# Infinity_Mirror_c_unbuilt.net
KiCad netlist of a schematic drawn in EAGLE
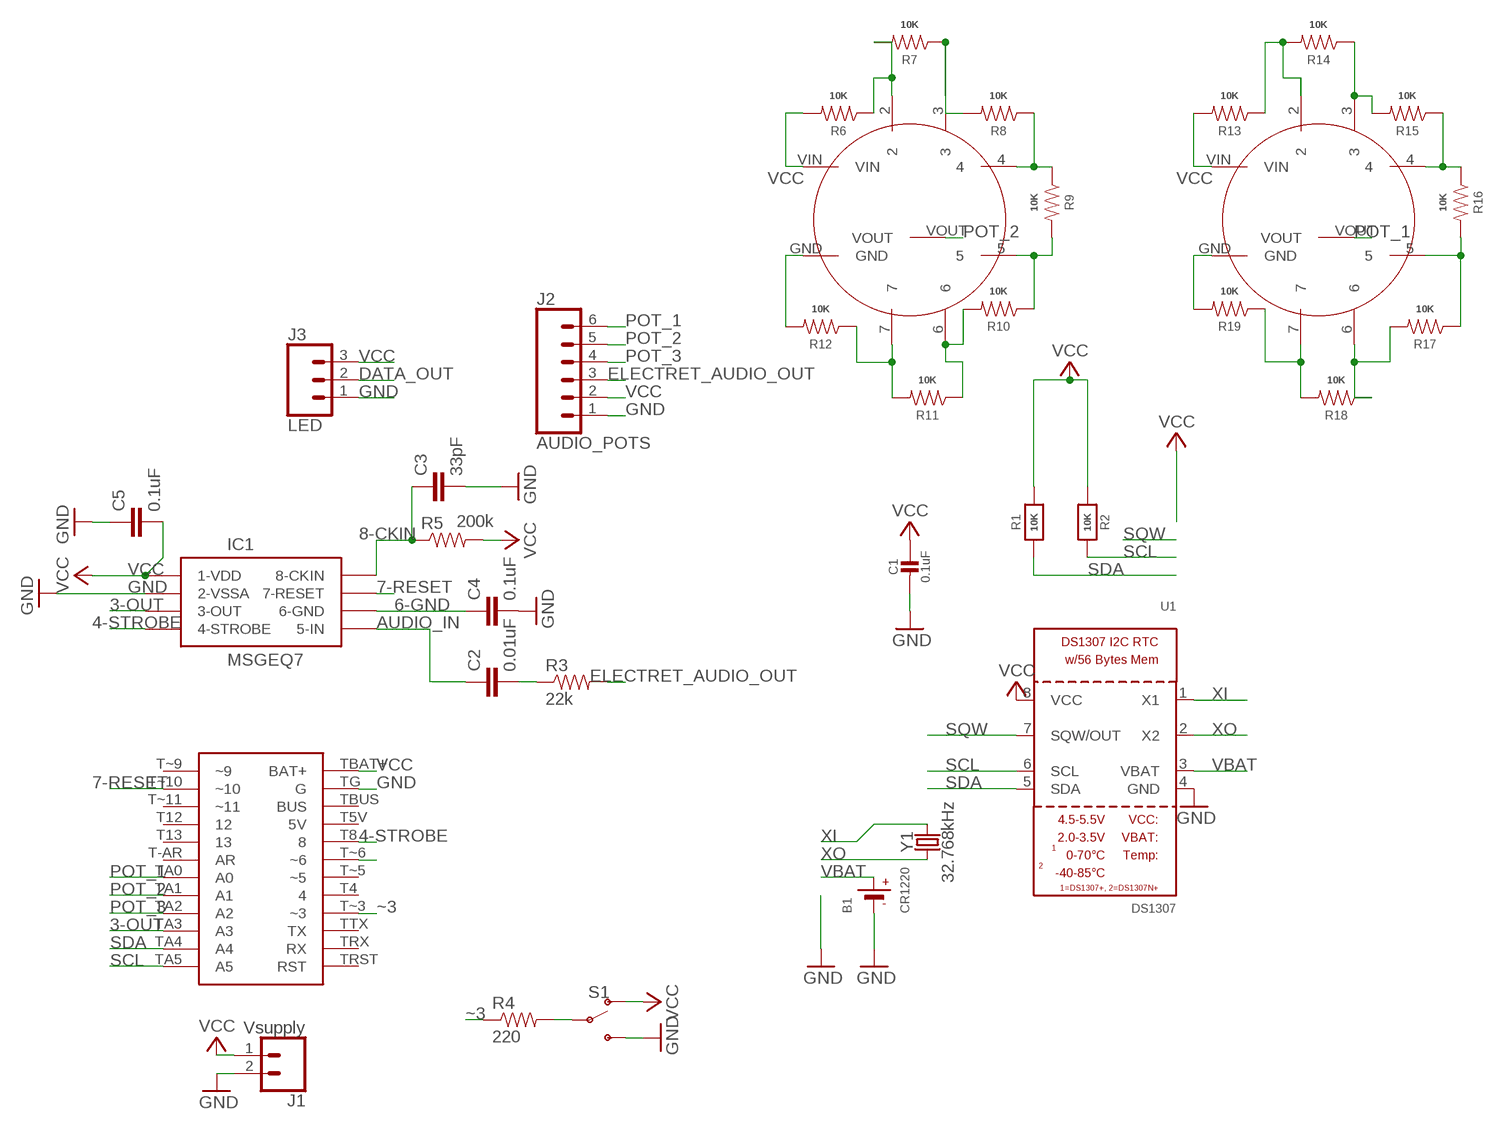
[diagram p0: schematic, sheet 1]

(export (version "E")
  (design (tool "Eeschema 10.0.6"))
  (components
    (comp (ref "B1")
      (value "CR1220")
      (footprint "eagle-import:CR1220")
      (libsource (lib "eagle-import") (part "BATTERYCR1220_SMT"))
    )
    (comp (ref "C1")
      (value "0.1uF")
      (footprint "eagle-import:0805-NO")
      (libsource (lib "eagle-import") (part "CAP_CERAMIC0805-NOOUTLINE"))
    )
    (comp (ref "C2")
      (value "0.01uF")
      (footprint "eagle-import:SPARKFUN-CAPACITORS_0805")
      (libsource (lib "eagle-import") (part "SPARKFUN-CAPACITORS_CAP0805"))
    )
    (comp (ref "C3")
      (value "33pF")
      (footprint "eagle-import:0805")
      (libsource (lib "eagle-import") (part "0.33UF/330NF-0805-50V-10%"))
    )
    (comp (ref "C4")
      (value "0.1uF")
      (footprint "eagle-import:SPARKFUN-CAPACITORS_0805")
      (libsource (lib "eagle-import") (part "SPARKFUN-CAPACITORS_CAP0805"))
    )
    (comp (ref "C5")
      (value "0.1uF")
      (footprint "eagle-import:SPARKFUN-CAPACITORS_0805")
      (libsource (lib "eagle-import") (part "SPARKFUN-CAPACITORS_CAP0805"))
    )
    (comp (ref "IC1")
      (value "MSGEQ7P")
      (footprint "eagle-import:DIP08")
      (libsource (lib "eagle-import") (part "MSGEQ7DIL"))
    )
    (comp (ref "J1")
      (value "Vsupply")
      (footprint "eagle-import:SPARKFUN-CONNECTORS_1X02_LOCK")
      (libsource (lib "eagle-import") (part "SPARKFUN-CONNECTORS_CONN_02LOCK"))
    )
    (comp (ref "J2")
      (value "AUDIO_POTS")
      (footprint "eagle-import:1X06")
      (libsource (lib "eagle-import") (part "CONN_06SILK_FEMALE_PTH"))
    )
    (comp (ref "J3")
      (value "LED")
      (footprint "eagle-import:1X03")
      (libsource (lib "eagle-import") (part "CONN_03"))
    )
    (comp (ref "R1")
      (value "10K")
      (footprint "eagle-import:0805-NO")
      (libsource (lib "eagle-import") (part "RESISTOR0805_NOOUTLINE"))
    )
    (comp (ref "R2")
      (value "10K")
      (footprint "eagle-import:0805-NO")
      (libsource (lib "eagle-import") (part "RESISTOR0805_NOOUTLINE"))
    )
    (comp (ref "R3")
      (value "22k")
      (footprint "eagle-import:SPARKFUN-PASSIVES_0805")
      (libsource (lib "eagle-import") (part "SPARKFUN-PASSIVES_RESISTOR0805-RES"))
    )
    (comp (ref "R4")
      (value "220")
      (footprint "eagle-import:SPARKFUN-PASSIVES_0805")
      (libsource (lib "eagle-import") (part "SPARKFUN-PASSIVES_RESISTOR0805-RES"))
    )
    (comp (ref "R5")
      (value "200k")
      (footprint "eagle-import:SPARKFUN-PASSIVES_0805")
      (libsource (lib "eagle-import") (part "SPARKFUN-PASSIVES_RESISTOR0805-RES"))
    )
    (comp (ref "R6")
      (value "10K")
      (footprint "eagle-import:SPARKFUN-PASSIVES_0805")
      (libsource (lib "eagle-import") (part "SPARKFUN-PASSIVES_RESISTOR0805-RES"))
    )
    (comp (ref "R7")
      (value "10K")
      (footprint "eagle-import:SPARKFUN-PASSIVES_0805")
      (libsource (lib "eagle-import") (part "SPARKFUN-PASSIVES_RESISTOR0805-RES"))
    )
    (comp (ref "R8")
      (value "10K")
      (footprint "eagle-import:SPARKFUN-PASSIVES_0805")
      (libsource (lib "eagle-import") (part "SPARKFUN-PASSIVES_RESISTOR0805-RES"))
    )
    (comp (ref "R9")
      (value "10K")
      (footprint "eagle-import:SPARKFUN-PASSIVES_0805")
      (libsource (lib "eagle-import") (part "SPARKFUN-PASSIVES_RESISTOR0805-RES"))
    )
    (comp (ref "R10")
      (value "10K")
      (footprint "eagle-import:SPARKFUN-PASSIVES_0805")
      (libsource (lib "eagle-import") (part "SPARKFUN-PASSIVES_RESISTOR0805-RES"))
    )
    (comp (ref "R11")
      (value "10K")
      (footprint "eagle-import:SPARKFUN-PASSIVES_0805")
      (libsource (lib "eagle-import") (part "SPARKFUN-PASSIVES_RESISTOR0805-RES"))
    )
    (comp (ref "R12")
      (value "10K")
      (footprint "eagle-import:SPARKFUN-PASSIVES_0805")
      (libsource (lib "eagle-import") (part "SPARKFUN-PASSIVES_RESISTOR0805-RES"))
    )
    (comp (ref "R13")
      (value "10K")
      (footprint "eagle-import:SPARKFUN-PASSIVES_0805")
      (libsource (lib "eagle-import") (part "SPARKFUN-PASSIVES_RESISTOR0805-RES"))
    )
    (comp (ref "R14")
      (value "10K")
      (footprint "eagle-import:SPARKFUN-PASSIVES_0805")
      (libsource (lib "eagle-import") (part "SPARKFUN-PASSIVES_RESISTOR0805-RES"))
    )
    (comp (ref "R15")
      (value "10K")
      (footprint "eagle-import:SPARKFUN-PASSIVES_0805")
      (libsource (lib "eagle-import") (part "SPARKFUN-PASSIVES_RESISTOR0805-RES"))
    )
    (comp (ref "R16")
      (value "10K")
      (footprint "eagle-import:SPARKFUN-PASSIVES_0805")
      (libsource (lib "eagle-import") (part "SPARKFUN-PASSIVES_RESISTOR0805-RES"))
    )
    (comp (ref "R17")
      (value "10K")
      (footprint "eagle-import:SPARKFUN-PASSIVES_0805")
      (libsource (lib "eagle-import") (part "SPARKFUN-PASSIVES_RESISTOR0805-RES"))
    )
    (comp (ref "R18")
      (value "10K")
      (footprint "eagle-import:SPARKFUN-PASSIVES_0805")
      (libsource (lib "eagle-import") (part "SPARKFUN-PASSIVES_RESISTOR0805-RES"))
    )
    (comp (ref "R19")
      (value "10K")
      (footprint "eagle-import:SPARKFUN-PASSIVES_0805")
      (libsource (lib "eagle-import") (part "SPARKFUN-PASSIVES_RESISTOR0805-RES"))
    )
    (comp (ref "S1")
      (value "SWITCH-SPDT-PTH-11.6X4.0MM-LOCK")
      (footprint "eagle-import:SWITCH_SPDT_PTH_11.6X4.0MM_LOCK")
      (libsource (lib "eagle-import") (part "SWITCH-SPDT-PTH-11.6X4.0MM-LOCK"))
    )
    (comp (ref "U$1")
      (value "ADAFRUIT_PRO_TRINKET_NO-DIMENSION")
      (footprint "eagle-import:ARDUINO_PRO_TRINKET_5V_NO-DIMENSION")
      (libsource (lib "eagle-import") (part "ADAFRUIT_PRO_TRINKET_NO-DIMENSION"))
    )
    (comp (ref "U$2")
      (value "ROTARY-SWITCH-8POS")
      (footprint "eagle-import:ROTARY-SWITCH-8POS")
      (libsource (lib "eagle-import") (part "ROTARY-SWITCH-8POS"))
    )
    (comp (ref "U$3")
      (value "ROTARY-SWITCH-8POS")
      (footprint "eagle-import:ROTARY-SWITCH-8POS")
      (libsource (lib "eagle-import") (part "ROTARY-SWITCH-8POS"))
    )
    (comp (ref "U1")
      (value "DS1307")
      (footprint "eagle-import:SOIC8_150MIL")
      (libsource (lib "eagle-import") (part "RTC_DS1307"))
    )
    (comp (ref "Y1")
      (value "32.768kHz")
      (footprint "eagle-import:CRYSTAL-PTH-2X6-CYL")
      (libsource (lib "eagle-import") (part "CRYSTAL-32.768KHZPTH-2X6"))
    )
  )
  (nets
    (net (code "1") (name "/3-OUT") (class "Default")
      (node (ref "IC1") (pin "3") (pinfunction "3-OUT_3") (pintype "input"))
      (node (ref "U$1") (pin "TA3") (pinfunction "A3_TA3") (pintype "bidirectional"))
    )
    (net (code "2") (name "/4-STROBE") (class "Default")
      (node (ref "IC1") (pin "4") (pinfunction "4-STROBE_4") (pintype "input"))
      (node (ref "U$1") (pin "T8") (pinfunction "8_T8") (pintype "bidirectional"))
    )
    (net (code "3") (name "/6-GND") (class "Default")
      (node (ref "C4") (pin "1") (pinfunction "1_1") (pintype "passive"))
      (node (ref "IC1") (pin "6") (pinfunction "6-GND_6") (pintype "bidirectional"))
    )
    (net (code "4") (name "/7-RESET") (class "Default")
      (node (ref "IC1") (pin "7") (pinfunction "7-RESET_7") (pintype "bidirectional"))
      (node (ref "U$1") (pin "T~10") (pinfunction "~{10}_T~10") (pintype "bidirectional"))
    )
    (net (code "5") (name "/8-CKIN") (class "Default")
      (node (ref "C3") (pin "1") (pinfunction "1_1") (pintype "passive"))
      (node (ref "IC1") (pin "8") (pinfunction "8-CKIN_8") (pintype "bidirectional"))
      (node (ref "R5") (pin "1") (pinfunction "1_1") (pintype "passive"))
    )
    (net (code "6") (name "/AUDIO_IN") (class "Default")
      (node (ref "C2") (pin "1") (pinfunction "1_1") (pintype "passive"))
      (node (ref "IC1") (pin "5") (pinfunction "5-IN_5") (pintype "bidirectional"))
    )
    (net (code "7") (name "/DATA_OUT") (class "Default")
      (node (ref "J3") (pin "2") (pinfunction "2_2") (pintype "passive"))
      (node (ref "U$1") (pin "T~6") (pinfunction "~{6}_T~6") (pintype "bidirectional"))
    )
    (net (code "8") (name "/ELECTRET_AUDIO_OUT") (class "Default")
      (node (ref "J2") (pin "3") (pinfunction "3_3") (pintype "passive"))
      (node (ref "R3") (pin "2") (pinfunction "2_2") (pintype "passive"))
    )
    (net (code "9") (name "/POT_1") (class "Default")
      (node (ref "J2") (pin "6") (pinfunction "6_6") (pintype "passive"))
      (node (ref "U$1") (pin "TA0") (pinfunction "A0_TA0") (pintype "bidirectional"))
      (node (ref "U$3") (pin "VOUT") (pinfunction "VOUT_VOUT") (pintype "bidirectional"))
    )
    (net (code "10") (name "/POT_2") (class "Default")
      (node (ref "J2") (pin "5") (pinfunction "5_5") (pintype "passive"))
      (node (ref "U$1") (pin "TA1") (pinfunction "A1_TA1") (pintype "bidirectional"))
      (node (ref "U$2") (pin "VOUT") (pinfunction "VOUT_VOUT") (pintype "bidirectional"))
    )
    (net (code "11") (name "/POT_3") (class "Default")
      (node (ref "J2") (pin "4") (pinfunction "4_4") (pintype "passive"))
      (node (ref "U$1") (pin "TA2") (pinfunction "A2_TA2") (pintype "bidirectional"))
    )
    (net (code "12") (name "/SCL") (class "Default")
      (node (ref "R2") (pin "2") (pinfunction "2_2") (pintype "passive"))
      (node (ref "U$1") (pin "TA5") (pinfunction "A5_TA5") (pintype "bidirectional"))
      (node (ref "U1") (pin "6") (pinfunction "SCL_6") (pintype "bidirectional"))
    )
    (net (code "13") (name "/SDA") (class "Default")
      (node (ref "R1") (pin "1") (pinfunction "1_1") (pintype "passive"))
      (node (ref "U$1") (pin "TA4") (pinfunction "A4_TA4") (pintype "bidirectional"))
      (node (ref "U1") (pin "5") (pinfunction "SDA_5") (pintype "bidirectional"))
    )
    (net (code "14") (name "/SQW") (class "Default")
      (node (ref "U1") (pin "7") (pinfunction "SQW/OUT_7") (pintype "bidirectional"))
    )
    (net (code "15") (name "/VBAT") (class "Default")
      (node (ref "B1") (pin "+$1") (pinfunction "+_+$1") (pintype "passive"))
      (node (ref "U1") (pin "3") (pinfunction "VBAT_3") (pintype "bidirectional"))
    )
    (net (code "16") (name "/XI") (class "Default")
      (node (ref "U1") (pin "1") (pinfunction "X1_1") (pintype "bidirectional"))
      (node (ref "Y1") (pin "2") (pinfunction "2_2") (pintype "passive"))
    )
    (net (code "17") (name "/XO") (class "Default")
      (node (ref "U1") (pin "2") (pinfunction "X2_2") (pintype "bidirectional"))
      (node (ref "Y1") (pin "1") (pinfunction "1_1") (pintype "passive"))
    )
    (net (code "18") (name "/~{3}") (class "Default")
      (node (ref "R4") (pin "1") (pinfunction "1_1") (pintype "passive"))
      (node (ref "U$1") (pin "T~3") (pinfunction "~{3}_T~3") (pintype "bidirectional"))
    )
    (net (code "19") (name "GND") (class "Default")
      (node (ref "B1") (pin "-") (pinfunction "-_-") (pintype "passive"))
      (node (ref "C1") (pin "2") (pinfunction "2_2") (pintype "passive"))
      (node (ref "C3") (pin "2") (pinfunction "2_2") (pintype "passive"))
      (node (ref "C4") (pin "2") (pinfunction "2_2") (pintype "passive"))
      (node (ref "C5") (pin "1") (pinfunction "1_1") (pintype "passive"))
      (node (ref "IC1") (pin "2") (pinfunction "2-VSSA_2") (pintype "input"))
      (node (ref "J1") (pin "2") (pinfunction "2_2") (pintype "passive"))
      (node (ref "J2") (pin "1") (pinfunction "1_1") (pintype "passive"))
      (node (ref "J3") (pin "1") (pinfunction "1_1") (pintype "passive"))
      (node (ref "S1") (pin "3") (pinfunction "S_3") (pintype "passive"))
      (node (ref "U$1") (pin "TG") (pinfunction "G_TG") (pintype "bidirectional"))
      (node (ref "U1") (pin "4") (pinfunction "GND_4") (pintype "bidirectional"))
    )
    (net (code "20") (name "Net-(C2-Pad2)") (class "Default")
      (node (ref "C2") (pin "2") (pinfunction "2_2") (pintype "passive"))
      (node (ref "R3") (pin "1") (pinfunction "1_1") (pintype "passive"))
    )
    (net (code "21") (name "Net-(R6-Pad1)") (class "Default")
      (node (ref "R6") (pin "1") (pinfunction "1_1") (pintype "passive"))
      (node (ref "R7") (pin "2") (pinfunction "2_2") (pintype "passive"))
      (node (ref "U$2") (pin "2") (pinfunction "2_2") (pintype "bidirectional"))
    )
    (net (code "22") (name "Net-(R7-Pad1)") (class "Default")
      (node (ref "R7") (pin "1") (pinfunction "1_1") (pintype "passive"))
      (node (ref "R8") (pin "2") (pinfunction "2_2") (pintype "passive"))
      (node (ref "U$2") (pin "3") (pinfunction "3_3") (pintype "bidirectional"))
    )
    (net (code "23") (name "Net-(R8-Pad1)") (class "Default")
      (node (ref "R8") (pin "1") (pinfunction "1_1") (pintype "passive"))
      (node (ref "R9") (pin "1") (pinfunction "1_1") (pintype "passive"))
      (node (ref "U$2") (pin "4") (pinfunction "4_4") (pintype "bidirectional"))
    )
    (net (code "24") (name "Net-(R10-Pad1)") (class "Default")
      (node (ref "R10") (pin "1") (pinfunction "1_1") (pintype "passive"))
      (node (ref "R9") (pin "2") (pinfunction "2_2") (pintype "passive"))
      (node (ref "U$2") (pin "5") (pinfunction "5_5") (pintype "bidirectional"))
    )
    (net (code "25") (name "Net-(R10-Pad2)") (class "Default")
      (node (ref "R10") (pin "2") (pinfunction "2_2") (pintype "passive"))
      (node (ref "R11") (pin "1") (pinfunction "1_1") (pintype "passive"))
      (node (ref "U$2") (pin "6") (pinfunction "6_6") (pintype "bidirectional"))
    )
    (net (code "26") (name "Net-(R11-Pad2)") (class "Default")
      (node (ref "R11") (pin "2") (pinfunction "2_2") (pintype "passive"))
      (node (ref "R12") (pin "1") (pinfunction "1_1") (pintype "passive"))
      (node (ref "U$2") (pin "7") (pinfunction "7_7") (pintype "bidirectional"))
    )
    (net (code "27") (name "Net-(R12-Pad2)") (class "Default")
      (node (ref "R12") (pin "2") (pinfunction "2_2") (pintype "passive"))
      (node (ref "U$2") (pin "GND") (pinfunction "GND_GND") (pintype "bidirectional"))
    )
    (net (code "28") (name "Net-(R13-Pad1)") (class "Default")
      (node (ref "R13") (pin "1") (pinfunction "1_1") (pintype "passive"))
      (node (ref "R14") (pin "2") (pinfunction "2_2") (pintype "passive"))
      (node (ref "U$3") (pin "2") (pinfunction "2_2") (pintype "bidirectional"))
    )
    (net (code "29") (name "Net-(R14-Pad1)") (class "Default")
      (node (ref "R14") (pin "1") (pinfunction "1_1") (pintype "passive"))
      (node (ref "R15") (pin "2") (pinfunction "2_2") (pintype "passive"))
      (node (ref "U$3") (pin "3") (pinfunction "3_3") (pintype "bidirectional"))
    )
    (net (code "30") (name "Net-(R15-Pad1)") (class "Default")
      (node (ref "R15") (pin "1") (pinfunction "1_1") (pintype "passive"))
      (node (ref "R16") (pin "1") (pinfunction "1_1") (pintype "passive"))
      (node (ref "U$3") (pin "4") (pinfunction "4_4") (pintype "bidirectional"))
    )
    (net (code "31") (name "Net-(R16-Pad2)") (class "Default")
      (node (ref "R16") (pin "2") (pinfunction "2_2") (pintype "passive"))
      (node (ref "R17") (pin "1") (pinfunction "1_1") (pintype "passive"))
      (node (ref "U$3") (pin "5") (pinfunction "5_5") (pintype "bidirectional"))
    )
    (net (code "32") (name "Net-(R17-Pad2)") (class "Default")
      (node (ref "R17") (pin "2") (pinfunction "2_2") (pintype "passive"))
      (node (ref "R18") (pin "1") (pinfunction "1_1") (pintype "passive"))
      (node (ref "U$3") (pin "6") (pinfunction "6_6") (pintype "bidirectional"))
    )
    (net (code "33") (name "Net-(R18-Pad2)") (class "Default")
      (node (ref "R18") (pin "2") (pinfunction "2_2") (pintype "passive"))
      (node (ref "R19") (pin "1") (pinfunction "1_1") (pintype "passive"))
      (node (ref "U$3") (pin "7") (pinfunction "7_7") (pintype "bidirectional"))
    )
    (net (code "34") (name "Net-(R19-Pad2)") (class "Default")
      (node (ref "R19") (pin "2") (pinfunction "2_2") (pintype "passive"))
      (node (ref "U$3") (pin "GND") (pinfunction "GND_GND") (pintype "bidirectional"))
    )
    (net (code "35") (name "Net-(S1-P)") (class "Default")
      (node (ref "R4") (pin "2") (pinfunction "2_2") (pintype "passive"))
      (node (ref "S1") (pin "2") (pinfunction "P_2") (pintype "passive"))
    )
    (net (code "36") (name "VCC") (class "Default")
      (node (ref "C1") (pin "1") (pinfunction "1_1") (pintype "passive"))
      (node (ref "C5") (pin "2") (pinfunction "2_2") (pintype "passive"))
      (node (ref "IC1") (pin "1") (pinfunction "1-VDD_1") (pintype "input"))
      (node (ref "J1") (pin "1") (pinfunction "1_1") (pintype "passive"))
      (node (ref "J2") (pin "2") (pinfunction "2_2") (pintype "passive"))
      (node (ref "J3") (pin "3") (pinfunction "3_3") (pintype "passive"))
      (node (ref "R1") (pin "2") (pinfunction "2_2") (pintype "passive"))
      (node (ref "R13") (pin "2") (pinfunction "2_2") (pintype "passive"))
      (node (ref "R2") (pin "1") (pinfunction "1_1") (pintype "passive"))
      (node (ref "R5") (pin "2") (pinfunction "2_2") (pintype "passive"))
      (node (ref "R6") (pin "2") (pinfunction "2_2") (pintype "passive"))
      (node (ref "S1") (pin "1") (pinfunction "O_1") (pintype "passive"))
      (node (ref "U$1") (pin "TBAT+") (pinfunction "BAT+_TBAT+") (pintype "bidirectional"))
      (node (ref "U$2") (pin "VIN") (pinfunction "VIN_VIN") (pintype "bidirectional"))
      (node (ref "U$3") (pin "VIN") (pinfunction "VIN_VIN") (pintype "bidirectional"))
      (node (ref "U1") (pin "8") (pinfunction "VCC_8") (pintype "bidirectional"))
    )
    (net (code "37") (name "unconnected-(U$1-4-PadT4)") (class "Default")
      (node (ref "U$1") (pin "T4") (pinfunction "4_T4") (pintype "bidirectional"))
    )
    (net (code "38") (name "unconnected-(U$1-5V-PadT5V)") (class "Default")
      (node (ref "U$1") (pin "T5V") (pinfunction "5V_T5V") (pintype "bidirectional"))
    )
    (net (code "39") (name "unconnected-(U$1-12-PadT12)") (class "Default")
      (node (ref "U$1") (pin "T12") (pinfunction "12_T12") (pintype "bidirectional"))
    )
    (net (code "40") (name "unconnected-(U$1-13-PadT13)") (class "Default")
      (node (ref "U$1") (pin "T13") (pinfunction "13_T13") (pintype "bidirectional"))
    )
    (net (code "41") (name "unconnected-(U$1-AR-PadT-AR)") (class "Default")
      (node (ref "U$1") (pin "T-AR") (pinfunction "AR_T-AR") (pintype "bidirectional"))
    )
    (net (code "42") (name "unconnected-(U$1-BUS-PadTBUS)") (class "Default")
      (node (ref "U$1") (pin "TBUS") (pinfunction "BUS_TBUS") (pintype "bidirectional"))
    )
    (net (code "43") (name "unconnected-(U$1-RST-PadTRST)") (class "Default")
      (node (ref "U$1") (pin "TRST") (pinfunction "RST_TRST") (pintype "bidirectional"))
    )
    (net (code "44") (name "unconnected-(U$1-RX-PadTRX)") (class "Default")
      (node (ref "U$1") (pin "TRX") (pinfunction "RX_TRX") (pintype "bidirectional"))
    )
    (net (code "45") (name "unconnected-(U$1-TX-PadTTX)") (class "Default")
      (node (ref "U$1") (pin "TTX") (pinfunction "TX_TTX") (pintype "bidirectional"))
    )
    (net (code "46") (name "unconnected-(U$1-~{5}-PadT~5)") (class "Default")
      (node (ref "U$1") (pin "T~5") (pinfunction "~{5}_T~5") (pintype "bidirectional"))
    )
    (net (code "47") (name "unconnected-(U$1-~{9}-PadT~9)") (class "Default")
      (node (ref "U$1") (pin "T~9") (pinfunction "~{9}_T~9") (pintype "bidirectional"))
    )
    (net (code "48") (name "unconnected-(U$1-~{11}-PadT~11)") (class "Default")
      (node (ref "U$1") (pin "T~11") (pinfunction "~{11}_T~11") (pintype "bidirectional"))
    )
  )
)
